# USB.net
KiCad netlist of a schematic drawn in Altium Designer
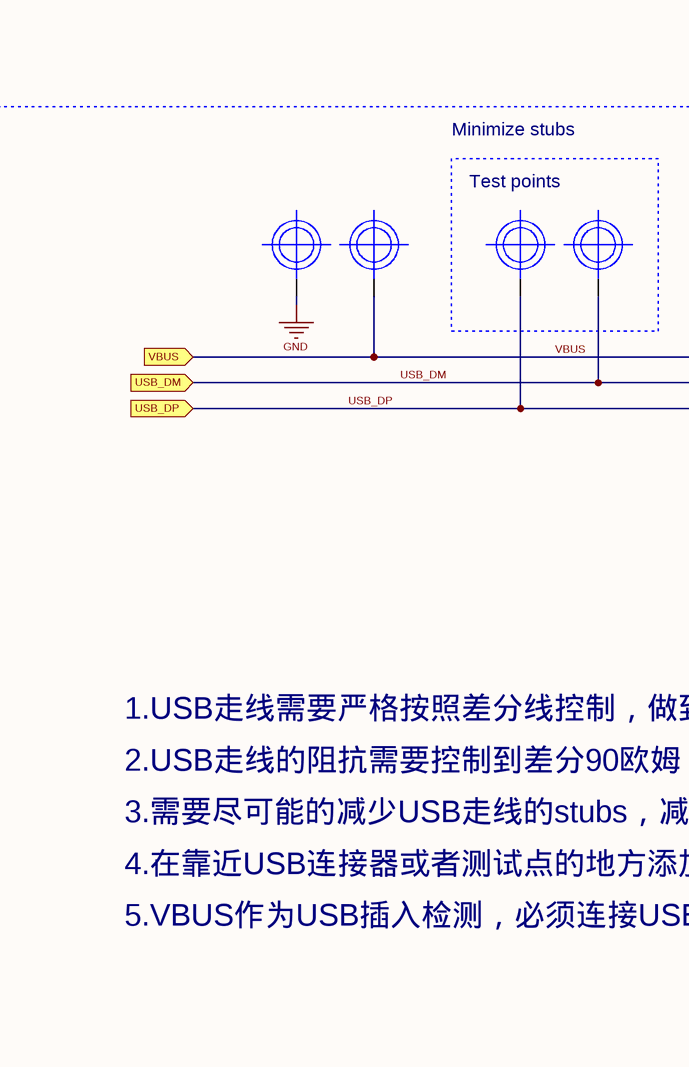
[diagram p0: USB.SchDoc, top left]
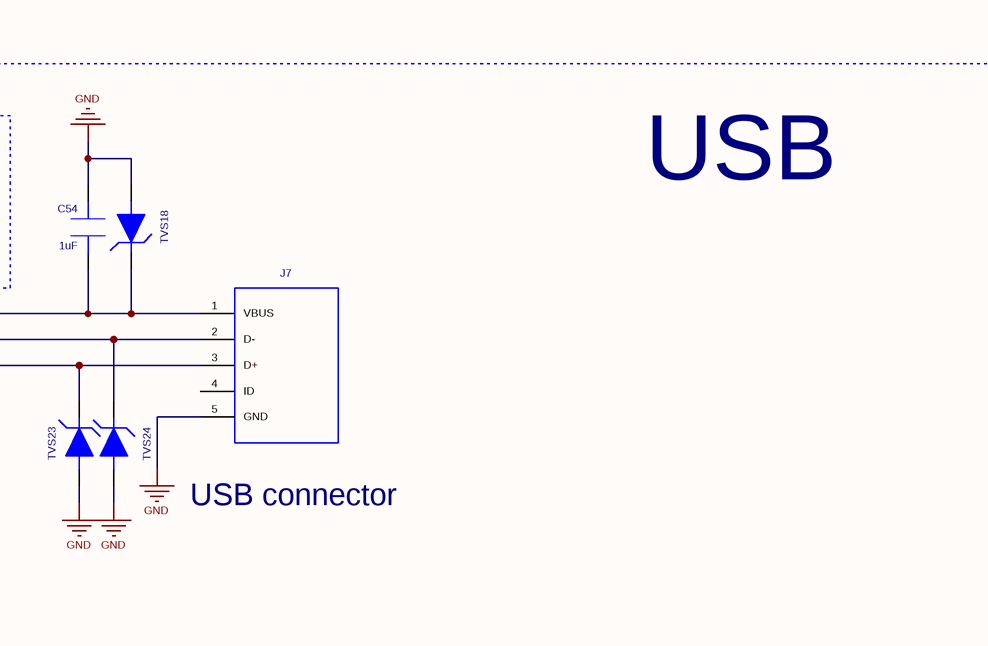
[diagram p1: USB.SchDoc, top middle]
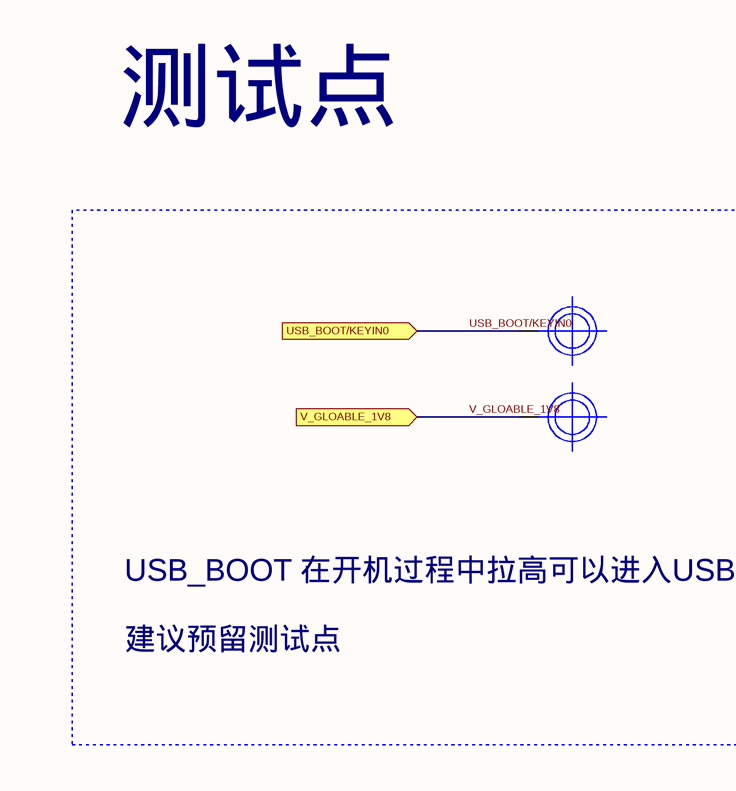
[diagram p2: USB.SchDoc, bottom left]
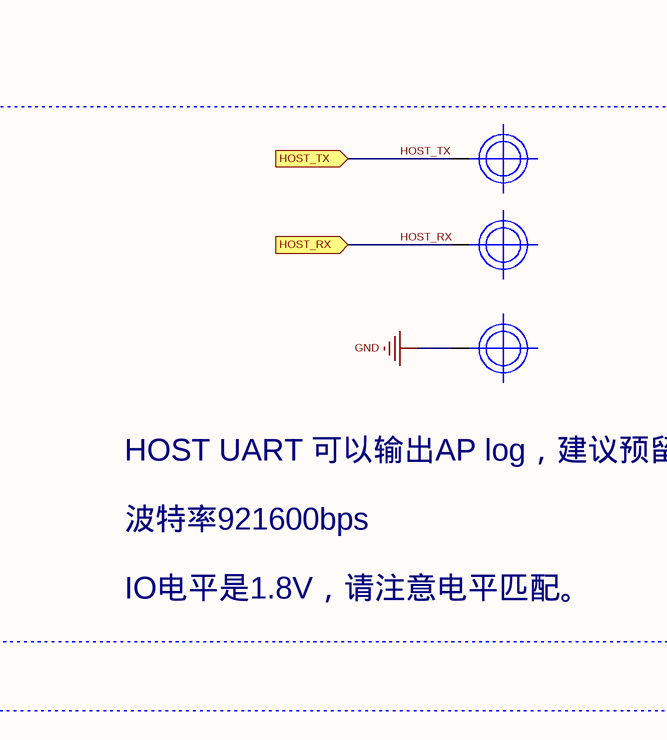
[diagram p3: USB.SchDoc, bottom middle]
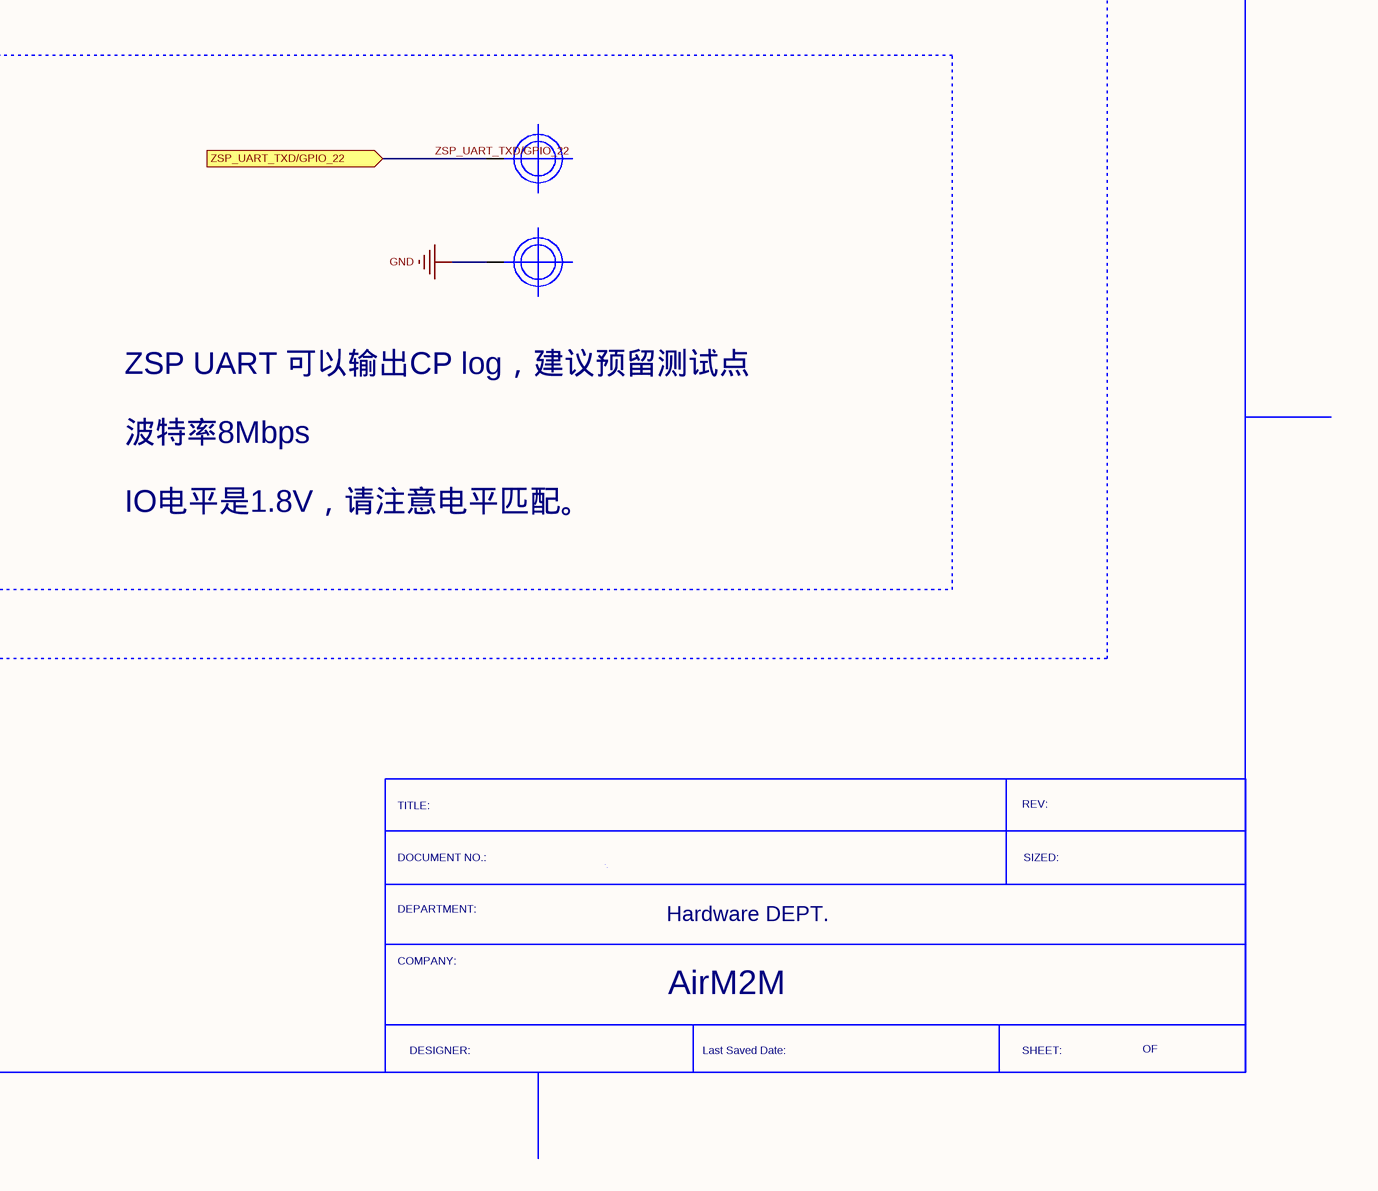
[diagram p4: USB.SchDoc, bottom right]

(export (version "E")
  (design (tool "Eeschema 10.0.6"))
  (components
    (comp (ref "C54")
      (value "1uF")
      (footprint "SC0402")
      (description "CAP CER X7R;1000PF;+/-10%;50V;0402;0.5mm;ROHS")
      (fields (field (name "TOLERANCE") "+/-10%") (field (name "Comment") "CAP-1000PF-0402-X7R"))
      (libsource (lib "*") (part "CAP-1000PF-0402-X7R"))
    )
    (comp (ref "J7")
      (value "USB-MICRO-10305060GSAR001")
      (footprint "USB90DEGREE")
      (description "Micro USB 5PIN;插板式;")
      (libsource (lib "*") (part "USB-MICRO-10305060GSAR001"))
    )
    (comp (ref "T1") (value "TESTPOINT") (footprint "TP1_5") (libsource (lib "*") (part "TESTPOINT")))
    (comp (ref "T2") (value "TESTPOINT") (footprint "TP1_5") (libsource (lib "*") (part "TESTPOINT")))
    (comp (ref "T3") (value "TESTPOINT") (footprint "TP1_5") (libsource (lib "*") (part "TESTPOINT")))
    (comp (ref "T4") (value "TESTPOINT") (footprint "TP1_5") (libsource (lib "*") (part "TESTPOINT")))
    (comp (ref "T5") (value "TESTPOINT") (footprint "TP1_5") (libsource (lib "*") (part "TESTPOINT")))
    (comp (ref "T6") (value "TESTPOINT") (footprint "TP1_5") (libsource (lib "*") (part "TESTPOINT")))
    (comp (ref "T7") (value "TESTPOINT") (footprint "TP1_5") (libsource (lib "*") (part "TESTPOINT")))
    (comp (ref "T8") (value "TESTPOINT") (footprint "TP1_5") (libsource (lib "*") (part "TESTPOINT")))
    (comp (ref "T9") (value "TESTPOINT") (footprint "TP1_5") (libsource (lib "*") (part "TESTPOINT")))
    (comp (ref "T10") (value "TESTPOINT") (footprint "TP1_5") (libsource (lib "*") (part "TESTPOINT")))
    (comp (ref "T11") (value "TESTPOINT") (footprint "TP1_5") (libsource (lib "*") (part "TESTPOINT")))
    (comp (ref "TVS18")
      (value "ESD-TVS-ESD9X7.0ST5G")
      (footprint "SOD-923-ESD9X5.0ST5G")
      (description "TVS;7.0V;65PF;SOD?923;ROHS")
      (libsource (lib "*") (part "ESD-TVS-ESD9X7.0ST5G"))
    )
    (comp (ref "TVS23")
      (value "ESD-TVS-ESD9L5.0T5G")
      (footprint "SOD-923-ESD9L5.0T5G")
      (description "TVS;5V;0.5pF;SOD-923;ROHS")
      (libsource (lib "*") (part "ESD-TVS-ESD9L5.0T5G"))
    )
    (comp (ref "TVS24")
      (value "ESD-TVS-ESD9L5.0T5G")
      (footprint "SOD-923-ESD9L5.0T5G")
      (description "TVS;5V;0.5pF;SOD-923;ROHS")
      (libsource (lib "*") (part "ESD-TVS-ESD9L5.0T5G"))
    )
  )
  (nets
    (net (code "1") (name "/HOST_RX") (class "Default")
      (node (ref "T8") (pin "1") (pinfunction "1_1") (pintype "passive"))
    )
    (net (code "2") (name "/HOST_TX") (class "Default")
      (node (ref "T7") (pin "1") (pinfunction "1_1") (pintype "passive"))
    )
    (net (code "3") (name "/USB_BOOT{slash}KEYIN0") (class "Default")
      (node (ref "T5") (pin "1") (pinfunction "1_1") (pintype "passive"))
    )
    (net (code "4") (name "/USB_DM") (class "Default")
      (node (ref "J7") (pin "2") (pinfunction "D-_2") (pintype "passive"))
      (node (ref "T2") (pin "1") (pinfunction "1_1") (pintype "passive"))
      (node (ref "TVS24") (pin "1") (pinfunction "1_1") (pintype "passive"))
    )
    (net (code "5") (name "/USB_DP") (class "Default")
      (node (ref "J7") (pin "3") (pinfunction "D+_3") (pintype "passive"))
      (node (ref "T1") (pin "1") (pinfunction "1_1") (pintype "passive"))
      (node (ref "TVS23") (pin "1") (pinfunction "1_1") (pintype "passive"))
    )
    (net (code "6") (name "/VBUS") (class "Default")
      (node (ref "C54") (pin "1") (pinfunction "1_1") (pintype "passive"))
      (node (ref "J7") (pin "1") (pinfunction "VBUS_1") (pintype "passive"))
      (node (ref "T4") (pin "1") (pinfunction "1_1") (pintype "passive"))
      (node (ref "TVS18") (pin "1") (pinfunction "1_1") (pintype "passive"))
    )
    (net (code "7") (name "/V_GLOABLE_1V8") (class "Default")
      (node (ref "T6") (pin "1") (pinfunction "1_1") (pintype "passive"))
    )
    (net (code "8") (name "/ZSP_UART_TXD{slash}GPIO_22") (class "Default")
      (node (ref "T10") (pin "1") (pinfunction "1_1") (pintype "passive"))
    )
    (net (code "9") (name "GND") (class "Default")
      (node (ref "C54") (pin "2") (pinfunction "2_2") (pintype "passive"))
      (node (ref "J7") (pin "5") (pinfunction "GND_5") (pintype "passive"))
      (node (ref "J7") (pin "6") (pinfunction "GND_6") (pintype "power_in"))
      (node (ref "J7") (pin "7") (pinfunction "GND_7") (pintype "power_in"))
      (node (ref "T11") (pin "1") (pinfunction "1_1") (pintype "passive"))
      (node (ref "T3") (pin "1") (pinfunction "1_1") (pintype "passive"))
      (node (ref "T9") (pin "1") (pinfunction "1_1") (pintype "passive"))
      (node (ref "TVS18") (pin "2") (pinfunction "2_2") (pintype "passive"))
      (node (ref "TVS23") (pin "2") (pinfunction "2_2") (pintype "passive"))
      (node (ref "TVS24") (pin "2") (pinfunction "2_2") (pintype "passive"))
    )
    (net (code "10") (name "unconnected-(J7-ID-Pad4)") (class "Default")
      (node (ref "J7") (pin "4") (pinfunction "ID_4") (pintype "passive"))
    )
  )
)
